# rakete.net
KiCad netlist of a schematic drawn in EAGLE
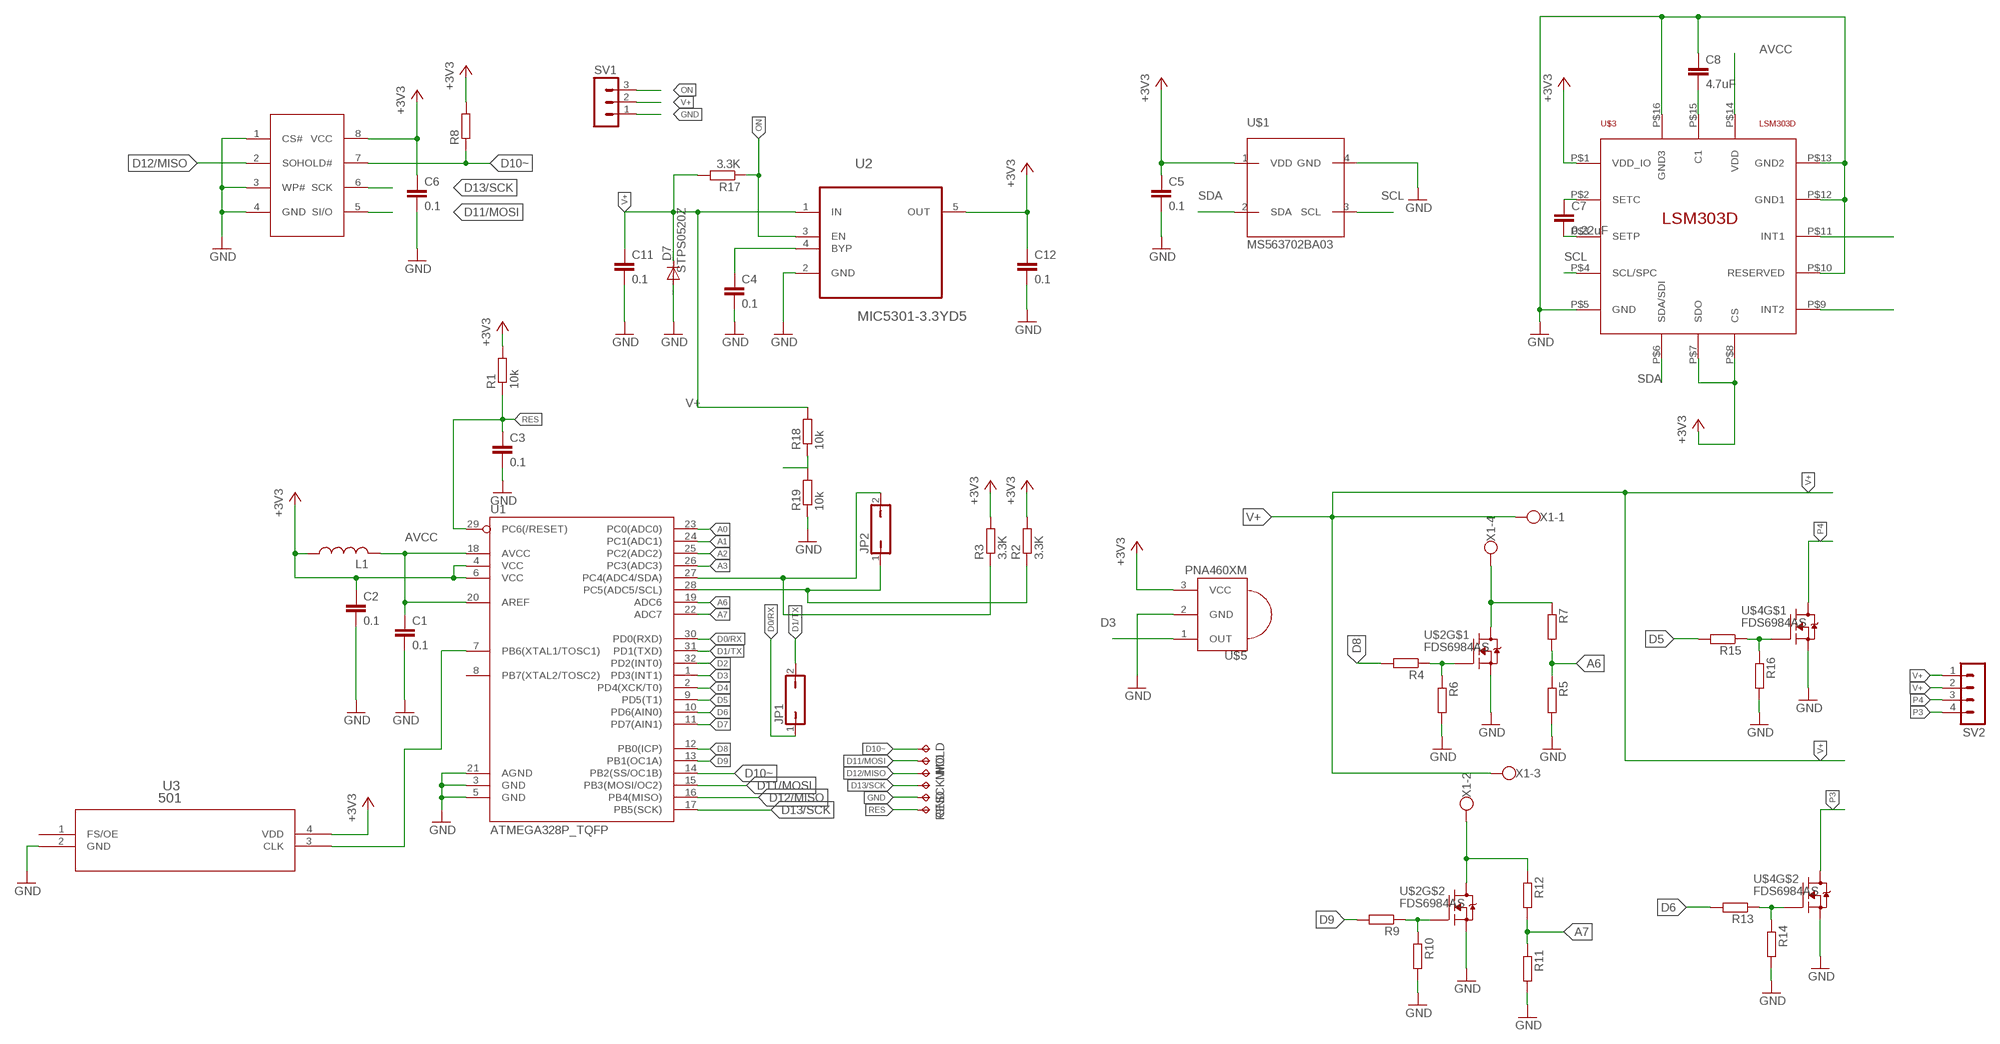
[diagram p0: schematic, sheet 1]

(export (version "E")
  (design (tool "Eeschema 10.0.6"))
  (components
    (comp (ref "C1")
      (value "0.1")
      (footprint "eagle-import:C0805")
      (libsource (lib "eagle-import") (part "resistor_C-EUC0805"))
    )
    (comp (ref "C2")
      (value "0.1")
      (footprint "eagle-import:C0805")
      (libsource (lib "eagle-import") (part "resistor_C-EUC0805"))
    )
    (comp (ref "C3")
      (value "0.1")
      (footprint "eagle-import:C0805")
      (libsource (lib "eagle-import") (part "resistor_C-EUC0805"))
    )
    (comp (ref "C4")
      (value "0.1")
      (footprint "eagle-import:C0805")
      (libsource (lib "eagle-import") (part "resistor_C-EUC0805"))
    )
    (comp (ref "C5")
      (value "0.1")
      (footprint "eagle-import:C0805")
      (libsource (lib "eagle-import") (part "resistor_C-EUC0805"))
    )
    (comp (ref "C6")
      (value "0.1")
      (footprint "eagle-import:C0805")
      (libsource (lib "eagle-import") (part "resistor_C-EUC0805"))
    )
    (comp (ref "C7")
      (value "0.22uF")
      (footprint "eagle-import:C0603")
      (libsource (lib "eagle-import") (part "C-EUC0603"))
    )
    (comp (ref "C8")
      (value "4.7uF")
      (footprint "eagle-import:C0603")
      (libsource (lib "eagle-import") (part "C-EUC0603"))
    )
    (comp (ref "C11")
      (value "0.1")
      (footprint "eagle-import:C0805")
      (libsource (lib "eagle-import") (part "resistor_C-EUC0805"))
    )
    (comp (ref "C12")
      (value "0.1")
      (footprint "eagle-import:C0805")
      (libsource (lib "eagle-import") (part "resistor_C-EUC0805"))
    )
    (comp (ref "D7")
      (value "CGRM4001-G")
      (footprint "eagle-import:SOD-123_MINI-SMA")
      (fields (field (name "MFGNAME") "STPS0520Z"))
      (libsource (lib "eagle-import") (part "CGRM400-G1"))
    )
    (comp (ref "GND")
      (value "TPB2,54")
      (footprint "eagle-import:B2,54")
      (libsource (lib "eagle-import") (part "TPB2,54"))
    )
    (comp (ref "HOLD")
      (value "TPB2,54")
      (footprint "eagle-import:B2,54")
      (libsource (lib "eagle-import") (part "TPB2,54"))
    )
    (comp (ref "JP1")
      (value "JP1Q")
      (footprint "eagle-import:JP1")
      (libsource (lib "eagle-import") (part "JP1Q"))
    )
    (comp (ref "JP2")
      (value "JP1Q")
      (footprint "eagle-import:JP1")
      (libsource (lib "eagle-import") (part "JP1Q"))
    )
    (comp (ref "L1")
      (value "L-USL2012C")
      (footprint "eagle-import:L2012C")
      (libsource (lib "eagle-import") (part "L-USL2012C"))
    )
    (comp (ref "MI")
      (value "TPB2,54")
      (footprint "eagle-import:B2,54")
      (libsource (lib "eagle-import") (part "TPB2,54"))
    )
    (comp (ref "MO")
      (value "TPB2,54")
      (footprint "eagle-import:B2,54")
      (libsource (lib "eagle-import") (part "TPB2,54"))
    )
    (comp (ref "R1")
      (value "10k")
      (footprint "eagle-import:R0805")
      (libsource (lib "eagle-import") (part "R-EU_R0805"))
    )
    (comp (ref "R2")
      (value "3.3K")
      (footprint "eagle-import:R0805")
      (libsource (lib "eagle-import") (part "R-EU_R0805"))
    )
    (comp (ref "R3")
      (value "3.3K")
      (footprint "eagle-import:R0805")
      (libsource (lib "eagle-import") (part "R-EU_R0805"))
    )
    (comp (ref "R4")
      (value "R-EU_R0805")
      (footprint "eagle-import:R0805")
      (libsource (lib "eagle-import") (part "R-EU_R0805"))
    )
    (comp (ref "R5")
      (value "R-EU_R0805")
      (footprint "eagle-import:R0805")
      (libsource (lib "eagle-import") (part "R-EU_R0805"))
    )
    (comp (ref "R6")
      (value "R-EU_R0805")
      (footprint "eagle-import:R0805")
      (libsource (lib "eagle-import") (part "R-EU_R0805"))
    )
    (comp (ref "R7")
      (value "R-EU_R0805")
      (footprint "eagle-import:R0805")
      (libsource (lib "eagle-import") (part "R-EU_R0805"))
    )
    (comp (ref "R8")
      (value "R-EU_R0805")
      (footprint "eagle-import:R0805")
      (libsource (lib "eagle-import") (part "R-EU_R0805"))
    )
    (comp (ref "R9")
      (value "R-EU_R0805")
      (footprint "eagle-import:R0805")
      (libsource (lib "eagle-import") (part "R-EU_R0805"))
    )
    (comp (ref "R10")
      (value "R-EU_R0805")
      (footprint "eagle-import:R0805")
      (libsource (lib "eagle-import") (part "R-EU_R0805"))
    )
    (comp (ref "R11")
      (value "R-EU_R0805")
      (footprint "eagle-import:R0805")
      (libsource (lib "eagle-import") (part "R-EU_R0805"))
    )
    (comp (ref "R12")
      (value "R-EU_R0805")
      (footprint "eagle-import:R0805")
      (libsource (lib "eagle-import") (part "R-EU_R0805"))
    )
    (comp (ref "R13")
      (value "R-EU_R0805")
      (footprint "eagle-import:R0805")
      (libsource (lib "eagle-import") (part "R-EU_R0805"))
    )
    (comp (ref "R14")
      (value "R-EU_R0805")
      (footprint "eagle-import:R0805")
      (libsource (lib "eagle-import") (part "R-EU_R0805"))
    )
    (comp (ref "R15")
      (value "R-EU_R0805")
      (footprint "eagle-import:R0805")
      (libsource (lib "eagle-import") (part "R-EU_R0805"))
    )
    (comp (ref "R16")
      (value "R-EU_R0805")
      (footprint "eagle-import:R0805")
      (libsource (lib "eagle-import") (part "R-EU_R0805"))
    )
    (comp (ref "R17")
      (value "3.3K")
      (footprint "eagle-import:R0805")
      (libsource (lib "eagle-import") (part "R-EU_R0805"))
    )
    (comp (ref "R18")
      (value "10k")
      (footprint "eagle-import:R0805")
      (libsource (lib "eagle-import") (part "R-EU_R0805"))
    )
    (comp (ref "R19")
      (value "10k")
      (footprint "eagle-import:R0805")
      (libsource (lib "eagle-import") (part "R-EU_R0805"))
    )
    (comp (ref "RE")
      (value "TPB2,54")
      (footprint "eagle-import:B2,54")
      (libsource (lib "eagle-import") (part "TPB2,54"))
    )
    (comp (ref "SCK")
      (value "TPB2,54")
      (footprint "eagle-import:B2,54")
      (libsource (lib "eagle-import") (part "TPB2,54"))
    )
    (comp (ref "SV1")
      (value "MA03-1")
      (footprint "eagle-import:MA03-1")
      (libsource (lib "eagle-import") (part "MA03-1"))
    )
    (comp (ref "SV2")
      (value "MA04-1")
      (footprint "eagle-import:MA04-1")
      (libsource (lib "eagle-import") (part "MA04-1"))
    )
    (comp (ref "U$1")
      (value "MS563702BA03")
      (footprint "eagle-import:MS5637")
      (libsource (lib "eagle-import") (part "MS563702BA03"))
    )
    (comp (ref "U$2")
      (value "FDS6984AS")
      (footprint "eagle-import:SO8")
      (fields
        (field (name "FARNELL") "2454158")
        (field (name "MFG") "FDS6984AS")
        (field (name "URL") "http://lv.farnell.com/fairchild-semiconductor/fds6984as/mosfet-dual-n-ch-30v-8-5a-soic/dp/2454158")
      )
      (libsource (lib "eagle-import") (part "FDS6984AS"))
    )
    (comp (ref "U$3")
      (value "LSM303D")
      (footprint "eagle-import:TFLGA16L")
      (libsource (lib "eagle-import") (part "LSM303D"))
    )
    (comp (ref "U$4")
      (value "FDS6984AS")
      (footprint "eagle-import:SO8")
      (fields
        (field (name "FARNELL") "2454158")
        (field (name "MFG") "FDS6984AS")
        (field (name "URL") "http://lv.farnell.com/fairchild-semiconductor/fds6984as/mosfet-dual-n-ch-30v-8-5a-soic/dp/2454158")
      )
      (libsource (lib "eagle-import") (part "FDS6984AS"))
    )
    (comp (ref "U$5")
      (value "PNA460XM")
      (footprint "eagle-import:PNA460XM")
      (libsource (lib "eagle-import") (part "PNA460XM"))
    )
    (comp (ref "U$6")
      (value "25FL208K0RMFI041")
      (footprint "eagle-import:SO08")
      (libsource (lib "eagle-import") (part "25FL208K0RMFI041"))
    )
    (comp (ref "U1")
      (value "ATMEGA328P_TQFP")
      (footprint "eagle-import:TQFP32-08")
      (libsource (lib "eagle-import") (part "ATMEGA328P_TQFP"))
    )
    (comp (ref "U2")
      (value "MIC5301-3.3YD5")
      (footprint "eagle-import:SOT95P280X130-5N")
      (fields
        (field (name "MPN") "MIC5205-3.3YM5TR")
        (field (name "MPN_1") "MIC5301-3.3YD5")
        (field (name "OC_FARNELL") "2431779")
      )
      (libsource (lib "eagle-import") (part "MIC5205-3.3YM5TR"))
    )
    (comp (ref "U3")
      (value "501")
      (footprint "eagle-import:SI501_4_2X2.5")
      (libsource (lib "eagle-import") (part "501"))
    )
    (comp (ref "X1")
      (value "W237-4")
      (footprint "eagle-import:W237-4")
      (libsource (lib "eagle-import") (part "W237-4"))
    )
  )
  (nets
    (net (code "1") (name "+3V3") (class "Default")
      (node (ref "C12") (pin "1") (pinfunction "1_1") (pintype "passive"))
      (node (ref "C2") (pin "1") (pinfunction "1_1") (pintype "passive"))
      (node (ref "C5") (pin "1") (pinfunction "1_1") (pintype "passive"))
      (node (ref "C6") (pin "1") (pinfunction "1_1") (pintype "passive"))
      (node (ref "L1") (pin "1") (pinfunction "1_1") (pintype "passive"))
      (node (ref "R1") (pin "2") (pinfunction "2_2") (pintype "passive"))
      (node (ref "R2") (pin "2") (pinfunction "2_2") (pintype "passive"))
      (node (ref "R3") (pin "2") (pinfunction "2_2") (pintype "passive"))
      (node (ref "R8") (pin "2") (pinfunction "2_2") (pintype "passive"))
      (node (ref "U$1") (pin "1") (pinfunction "VDD_1") (pintype "bidirectional"))
      (node (ref "U$3") (pin "P$1") (pinfunction "VDD_IO_P$1") (pintype "power_in"))
      (node (ref "U$3") (pin "P$7") (pinfunction "SDO_P$7") (pintype "bidirectional"))
      (node (ref "U$3") (pin "P$8") (pinfunction "CS_P$8") (pintype "bidirectional"))
      (node (ref "U$5") (pin "3") (pinfunction "VCC_3") (pintype "power_in"))
      (node (ref "U$6") (pin "8") (pinfunction "VCC_8") (pintype "power_in"))
      (node (ref "U1") (pin "4") (pinfunction "VCC_4") (pintype "bidirectional"))
      (node (ref "U1") (pin "6") (pinfunction "VCC_6") (pintype "bidirectional"))
      (node (ref "U2") (pin "5") (pinfunction "OUT_5") (pintype "output"))
      (node (ref "U3") (pin "4") (pinfunction "VDD_4") (pintype "power_in"))
    )
    (net (code "2") (name "/AVCC") (class "Default")
      (node (ref "C1") (pin "1") (pinfunction "1_1") (pintype "passive"))
      (node (ref "L1") (pin "2") (pinfunction "2_2") (pintype "passive"))
      (node (ref "U$3") (pin "P$14") (pinfunction "VDD_P$14") (pintype "bidirectional"))
      (node (ref "U1") (pin "18") (pinfunction "AVCC_18") (pintype "bidirectional"))
      (node (ref "U1") (pin "20") (pinfunction "AREF_20") (pintype "bidirectional"))
    )
    (net (code "3") (name "/D10~{}") (class "Default")
      (node (ref "HOLD") (pin "TP") (pinfunction "TP_TP") (pintype "input"))
      (node (ref "R8") (pin "1") (pinfunction "1_1") (pintype "passive"))
      (node (ref "U$6") (pin "7") (pinfunction "HOLD#_7") (pintype "input"))
      (node (ref "U1") (pin "14") (pinfunction "PB2(SS/OC1B)_14") (pintype "bidirectional"))
    )
    (net (code "4") (name "/SCL") (class "Default")
      (node (ref "JP2") (pin "1") (pinfunction "1_1") (pintype "passive"))
      (node (ref "R2") (pin "1") (pinfunction "1_1") (pintype "passive"))
      (node (ref "U$1") (pin "3") (pinfunction "SCL_3") (pintype "bidirectional"))
      (node (ref "U$3") (pin "P$4") (pinfunction "SCL/SPC_P$4") (pintype "bidirectional"))
      (node (ref "U1") (pin "28") (pinfunction "PC5(ADC5/SCL)_28") (pintype "bidirectional"))
    )
    (net (code "5") (name "/SDA") (class "Default")
      (node (ref "JP2") (pin "2") (pinfunction "2_2") (pintype "passive"))
      (node (ref "R3") (pin "1") (pinfunction "1_1") (pintype "passive"))
      (node (ref "U$1") (pin "2") (pinfunction "SDA_2") (pintype "bidirectional"))
      (node (ref "U$3") (pin "P$6") (pinfunction "SDA/SDI_P$6") (pintype "bidirectional"))
      (node (ref "U1") (pin "27") (pinfunction "PC4(ADC4/SDA)_27") (pintype "bidirectional"))
    )
    (net (code "6") (name "A0") (class "Default")
      (node (ref "U1") (pin "23") (pinfunction "PC0(ADC0)_23") (pintype "bidirectional"))
    )
    (net (code "7") (name "A1") (class "Default")
      (node (ref "R18") (pin "1") (pinfunction "1_1") (pintype "passive"))
      (node (ref "R19") (pin "2") (pinfunction "2_2") (pintype "passive"))
      (node (ref "U1") (pin "24") (pinfunction "PC1(ADC1)_24") (pintype "bidirectional"))
    )
    (net (code "8") (name "A2") (class "Default")
      (node (ref "U1") (pin "25") (pinfunction "PC2(ADC2)_25") (pintype "bidirectional"))
    )
    (net (code "9") (name "A3") (class "Default")
      (node (ref "U1") (pin "26") (pinfunction "PC3(ADC3)_26") (pintype "bidirectional"))
    )
    (net (code "10") (name "A6") (class "Default")
      (node (ref "R5") (pin "1") (pinfunction "1_1") (pintype "passive"))
      (node (ref "R7") (pin "2") (pinfunction "2_2") (pintype "passive"))
      (node (ref "U1") (pin "19") (pinfunction "ADC6_19") (pintype "bidirectional"))
    )
    (net (code "11") (name "A7") (class "Default")
      (node (ref "R11") (pin "1") (pinfunction "1_1") (pintype "passive"))
      (node (ref "R12") (pin "2") (pinfunction "2_2") (pintype "passive"))
      (node (ref "U1") (pin "22") (pinfunction "ADC7_22") (pintype "bidirectional"))
    )
    (net (code "12") (name "D0{slash}RX") (class "Default")
      (node (ref "JP1") (pin "1") (pinfunction "1_1") (pintype "passive"))
      (node (ref "U1") (pin "30") (pinfunction "PD0(RXD)_30") (pintype "bidirectional"))
    )
    (net (code "13") (name "D1{slash}TX") (class "Default")
      (node (ref "JP1") (pin "2") (pinfunction "2_2") (pintype "passive"))
      (node (ref "U1") (pin "31") (pinfunction "PD1(TXD)_31") (pintype "bidirectional"))
    )
    (net (code "14") (name "D2") (class "Default")
      (node (ref "U1") (pin "32") (pinfunction "PD2(INT0)_32") (pintype "bidirectional"))
    )
    (net (code "15") (name "D3") (class "Default")
      (node (ref "U$5") (pin "1") (pinfunction "OUT_1") (pintype "output"))
      (node (ref "U1") (pin "1") (pinfunction "PD3(INT1)_1") (pintype "bidirectional"))
    )
    (net (code "16") (name "D4") (class "Default")
      (node (ref "U1") (pin "2") (pinfunction "PD4(XCK/T0)_2") (pintype "bidirectional"))
    )
    (net (code "17") (name "D5") (class "Default")
      (node (ref "R15") (pin "2") (pinfunction "2_2") (pintype "passive"))
      (node (ref "U1") (pin "9") (pinfunction "PD5(T1)_9") (pintype "bidirectional"))
    )
    (net (code "18") (name "D6") (class "Default")
      (node (ref "R13") (pin "2") (pinfunction "2_2") (pintype "passive"))
      (node (ref "U1") (pin "10") (pinfunction "PD6(AIN0)_10") (pintype "bidirectional"))
    )
    (net (code "19") (name "D7") (class "Default")
      (node (ref "U1") (pin "11") (pinfunction "PD7(AIN1)_11") (pintype "bidirectional"))
    )
    (net (code "20") (name "D8") (class "Default")
      (node (ref "R4") (pin "2") (pinfunction "2_2") (pintype "passive"))
      (node (ref "U1") (pin "12") (pinfunction "PB0(ICP)_12") (pintype "bidirectional"))
    )
    (net (code "21") (name "D9") (class "Default")
      (node (ref "R9") (pin "2") (pinfunction "2_2") (pintype "passive"))
      (node (ref "U1") (pin "13") (pinfunction "PB1(OC1A)_13") (pintype "bidirectional"))
    )
    (net (code "22") (name "D11{slash}MOSI") (class "Default")
      (node (ref "MO") (pin "TP") (pinfunction "TP_TP") (pintype "input"))
      (node (ref "U$6") (pin "5") (pinfunction "SI/O_5") (pintype "bidirectional"))
      (node (ref "U1") (pin "15") (pinfunction "PB3(MOSI/OC2)_15") (pintype "bidirectional"))
    )
    (net (code "23") (name "D12{slash}MISO") (class "Default")
      (node (ref "MI") (pin "TP") (pinfunction "TP_TP") (pintype "input"))
      (node (ref "U$6") (pin "2") (pinfunction "SO_2") (pintype "output"))
      (node (ref "U1") (pin "16") (pinfunction "PB4(MISO)_16") (pintype "bidirectional"))
    )
    (net (code "24") (name "D13{slash}SCK") (class "Default")
      (node (ref "SCK") (pin "TP") (pinfunction "TP_TP") (pintype "input"))
      (node (ref "U$6") (pin "6") (pinfunction "SCK_6") (pintype "input"))
      (node (ref "U1") (pin "17") (pinfunction "PB5(SCK)_17") (pintype "bidirectional"))
    )
    (net (code "25") (name "GND") (class "Default")
      (node (ref "C1") (pin "2") (pinfunction "2_2") (pintype "passive"))
      (node (ref "C11") (pin "2") (pinfunction "2_2") (pintype "passive"))
      (node (ref "C12") (pin "2") (pinfunction "2_2") (pintype "passive"))
      (node (ref "C2") (pin "2") (pinfunction "2_2") (pintype "passive"))
      (node (ref "C3") (pin "2") (pinfunction "2_2") (pintype "passive"))
      (node (ref "C4") (pin "2") (pinfunction "2_2") (pintype "passive"))
      (node (ref "C5") (pin "2") (pinfunction "2_2") (pintype "passive"))
      (node (ref "C6") (pin "2") (pinfunction "2_2") (pintype "passive"))
      (node (ref "C8") (pin "1") (pinfunction "1_1") (pintype "passive"))
      (node (ref "D7") (pin "A") (pinfunction "A_A") (pintype "passive"))
      (node (ref "GND") (pin "TP") (pinfunction "TP_TP") (pintype "input"))
      (node (ref "R10") (pin "2") (pinfunction "2_2") (pintype "passive"))
      (node (ref "R11") (pin "2") (pinfunction "2_2") (pintype "passive"))
      (node (ref "R14") (pin "2") (pinfunction "2_2") (pintype "passive"))
      (node (ref "R16") (pin "2") (pinfunction "2_2") (pintype "passive"))
      (node (ref "R19") (pin "1") (pinfunction "1_1") (pintype "passive"))
      (node (ref "R5") (pin "2") (pinfunction "2_2") (pintype "passive"))
      (node (ref "R6") (pin "2") (pinfunction "2_2") (pintype "passive"))
      (node (ref "SV1") (pin "1") (pinfunction "1_1") (pintype "passive"))
      (node (ref "U$1") (pin "4") (pinfunction "GND_4") (pintype "bidirectional"))
      (node (ref "U$2") (pin "1") (pinfunction "S_1") (pintype "passive"))
      (node (ref "U$2") (pin "3") (pinfunction "S_3") (pintype "passive"))
      (node (ref "U$3") (pin "P$10") (pinfunction "RESERVED_P$10") (pintype "bidirectional"))
      (node (ref "U$3") (pin "P$12") (pinfunction "GND1_P$12") (pintype "power_in"))
      (node (ref "U$3") (pin "P$13") (pinfunction "GND2_P$13") (pintype "bidirectional"))
      (node (ref "U$3") (pin "P$16") (pinfunction "GND3_P$16") (pintype "bidirectional"))
      (node (ref "U$3") (pin "P$5") (pinfunction "GND_P$5") (pintype "power_in"))
      (node (ref "U$4") (pin "1") (pinfunction "S_1") (pintype "passive"))
      (node (ref "U$4") (pin "3") (pinfunction "S_3") (pintype "passive"))
      (node (ref "U$5") (pin "2") (pinfunction "GND_2") (pintype "power_in"))
      (node (ref "U$6") (pin "1") (pinfunction "CS#_1") (pintype "input"))
      (node (ref "U$6") (pin "3") (pinfunction "WP#_3") (pintype "input"))
      (node (ref "U$6") (pin "4") (pinfunction "GND_4") (pintype "power_in"))
      (node (ref "U1") (pin "21") (pinfunction "AGND_21") (pintype "bidirectional"))
      (node (ref "U1") (pin "3") (pinfunction "GND_3") (pintype "bidirectional"))
      (node (ref "U1") (pin "5") (pinfunction "GND_5") (pintype "bidirectional"))
      (node (ref "U2") (pin "2") (pinfunction "GND_2") (pintype "passive"))
      (node (ref "U3") (pin "2") (pinfunction "GND_2") (pintype "power_in"))
    )
    (net (code "26") (name "Net-(U$2A-G)") (class "Default")
      (node (ref "R4") (pin "1") (pinfunction "1_1") (pintype "passive"))
      (node (ref "R6") (pin "1") (pinfunction "1_1") (pintype "passive"))
      (node (ref "U$2") (pin "4") (pinfunction "G_4") (pintype "passive"))
    )
    (net (code "27") (name "Net-(U$2B-G)") (class "Default")
      (node (ref "R10") (pin "1") (pinfunction "1_1") (pintype "passive"))
      (node (ref "R9") (pin "1") (pinfunction "1_1") (pintype "passive"))
      (node (ref "U$2") (pin "2") (pinfunction "G_2") (pintype "passive"))
    )
    (net (code "28") (name "Net-(U$3-C1)") (class "Default")
      (node (ref "C8") (pin "2") (pinfunction "2_2") (pintype "passive"))
      (node (ref "U$3") (pin "P$15") (pinfunction "C1_P$15") (pintype "bidirectional"))
    )
    (net (code "29") (name "Net-(U$3-SETC)") (class "Default")
      (node (ref "C7") (pin "1") (pinfunction "1_1") (pintype "passive"))
      (node (ref "U$3") (pin "P$2") (pinfunction "SETC_P$2") (pintype "bidirectional"))
    )
    (net (code "30") (name "Net-(U$3-SETP)") (class "Default")
      (node (ref "C7") (pin "2") (pinfunction "2_2") (pintype "passive"))
      (node (ref "U$3") (pin "P$3") (pinfunction "SETP_P$3") (pintype "bidirectional"))
    )
    (net (code "31") (name "Net-(U$4A-G)") (class "Default")
      (node (ref "R15") (pin "1") (pinfunction "1_1") (pintype "passive"))
      (node (ref "R16") (pin "1") (pinfunction "1_1") (pintype "passive"))
      (node (ref "U$4") (pin "4") (pinfunction "G_4") (pintype "passive"))
    )
    (net (code "32") (name "Net-(U$4B-G)") (class "Default")
      (node (ref "R13") (pin "1") (pinfunction "1_1") (pintype "passive"))
      (node (ref "R14") (pin "1") (pinfunction "1_1") (pintype "passive"))
      (node (ref "U$4") (pin "2") (pinfunction "G_2") (pintype "passive"))
    )
    (net (code "33") (name "Net-(U1-PB6(XTAL1{slash}TOSC1))") (class "Default")
      (node (ref "U1") (pin "7") (pinfunction "PB6(XTAL1/TOSC1)_7") (pintype "bidirectional"))
      (node (ref "U3") (pin "3") (pinfunction "CLK_3") (pintype "output"))
    )
    (net (code "34") (name "Net-(U2-BYP)") (class "Default")
      (node (ref "C4") (pin "1") (pinfunction "1_1") (pintype "passive"))
      (node (ref "U2") (pin "4") (pinfunction "BYP_4") (pintype "input"))
    )
    (net (code "35") (name "Net-(X1B-KL)") (class "Default")
      (node (ref "R12") (pin "1") (pinfunction "1_1") (pintype "passive"))
      (node (ref "U$2") (pin "7") (pinfunction "D_7") (pintype "passive"))
      (node (ref "U$2") (pin "8") (pinfunction "D_8") (pintype "passive"))
      (node (ref "X1") (pin "2") (pinfunction "KL_2") (pintype "passive"))
    )
    (net (code "36") (name "Net-(X1D-KL)") (class "Default")
      (node (ref "R7") (pin "1") (pinfunction "1_1") (pintype "passive"))
      (node (ref "U$2") (pin "5") (pinfunction "D_5") (pintype "passive"))
      (node (ref "U$2") (pin "6") (pinfunction "D_6") (pintype "passive"))
      (node (ref "X1") (pin "4") (pinfunction "KL_4") (pintype "passive"))
    )
    (net (code "37") (name "ON") (class "Default")
      (node (ref "R17") (pin "1") (pinfunction "1_1") (pintype "passive"))
      (node (ref "SV1") (pin "3") (pinfunction "3_3") (pintype "passive"))
      (node (ref "U2") (pin "3") (pinfunction "EN_3") (pintype "input"))
    )
    (net (code "38") (name "P3") (class "Default")
      (node (ref "SV2") (pin "4") (pinfunction "4_4") (pintype "passive"))
      (node (ref "U$4") (pin "7") (pinfunction "D_7") (pintype "passive"))
      (node (ref "U$4") (pin "8") (pinfunction "D_8") (pintype "passive"))
    )
    (net (code "39") (name "P4") (class "Default")
      (node (ref "SV2") (pin "3") (pinfunction "3_3") (pintype "passive"))
      (node (ref "U$4") (pin "5") (pinfunction "D_5") (pintype "passive"))
      (node (ref "U$4") (pin "6") (pinfunction "D_6") (pintype "passive"))
    )
    (net (code "40") (name "RES") (class "Default")
      (node (ref "C3") (pin "1") (pinfunction "1_1") (pintype "passive"))
      (node (ref "R1") (pin "1") (pinfunction "1_1") (pintype "passive"))
      (node (ref "RE") (pin "TP") (pinfunction "TP_TP") (pintype "input"))
      (node (ref "U1") (pin "29") (pinfunction "PC6(/RESET)_29") (pintype "bidirectional"))
    )
    (net (code "41") (name "V+") (class "Default")
      (node (ref "C11") (pin "1") (pinfunction "1_1") (pintype "passive"))
      (node (ref "D7") (pin "C") (pinfunction "C_C") (pintype "passive"))
      (node (ref "R17") (pin "2") (pinfunction "2_2") (pintype "passive"))
      (node (ref "R18") (pin "2") (pinfunction "2_2") (pintype "passive"))
      (node (ref "SV1") (pin "2") (pinfunction "2_2") (pintype "passive"))
      (node (ref "SV2") (pin "1") (pinfunction "1_1") (pintype "passive"))
      (node (ref "SV2") (pin "2") (pinfunction "2_2") (pintype "passive"))
      (node (ref "U2") (pin "1") (pinfunction "IN_1") (pintype "input"))
      (node (ref "X1") (pin "1") (pinfunction "KL_1") (pintype "passive"))
      (node (ref "X1") (pin "3") (pinfunction "KL_3") (pintype "passive"))
    )
    (net (code "42") (name "unconnected-(U$3-INT1-PadP$11)") (class "Default")
      (node (ref "U$3") (pin "P$11") (pinfunction "INT1_P$11") (pintype "bidirectional"))
    )
    (net (code "43") (name "unconnected-(U$3-INT2-PadP$9)") (class "Default")
      (node (ref "U$3") (pin "P$9") (pinfunction "INT2_P$9") (pintype "bidirectional"))
    )
    (net (code "44") (name "unconnected-(U1-PB7(XTAL2{slash}TOSC2)-Pad8)") (class "Default")
      (node (ref "U1") (pin "8") (pinfunction "PB7(XTAL2/TOSC2)_8") (pintype "bidirectional"))
    )
    (net (code "45") (name "unconnected-(U3-FS{slash}OE-Pad1)") (class "Default")
      (node (ref "U3") (pin "1") (pinfunction "FS/OE_1") (pintype "passive"))
    )
  )
)
